# Power_Supply.net
KiCad netlist of a schematic drawn in Altium Designer
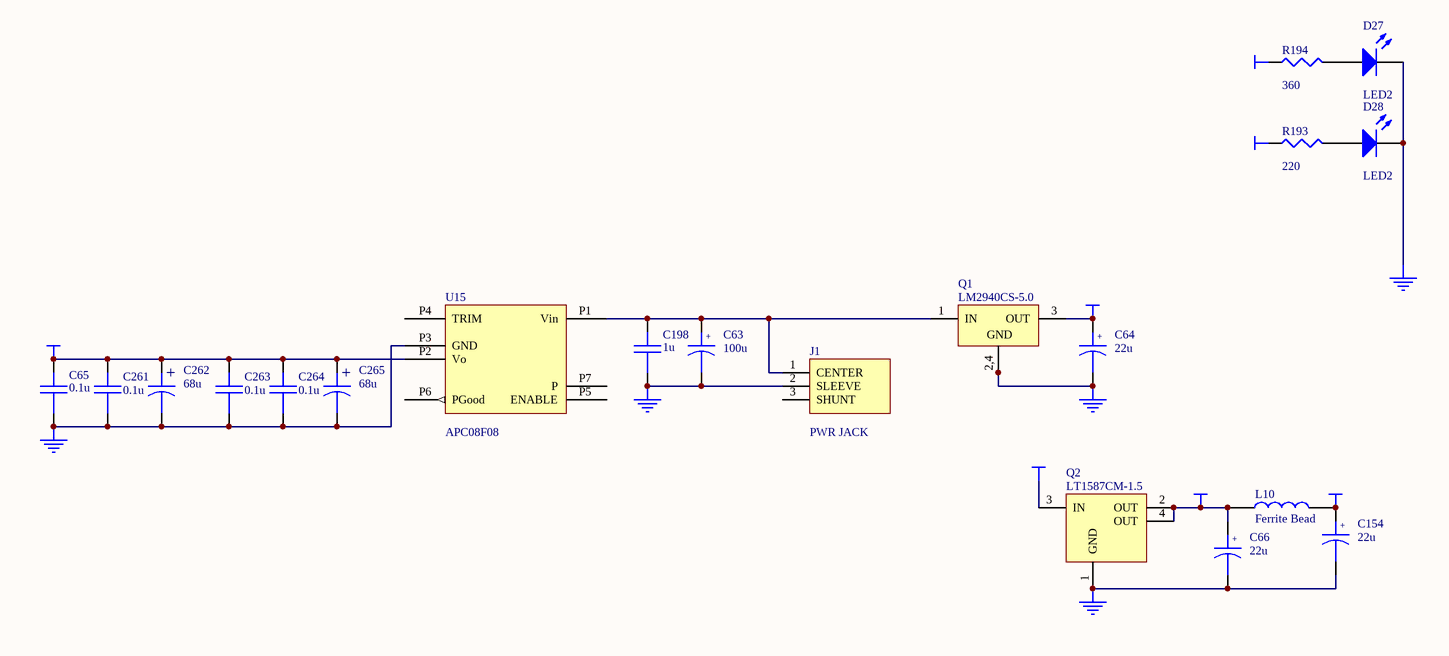
[diagram p0: Power Supply.SchDoc]

(export (version "E")
  (design (tool "Eeschema 10.0.6"))
  (components
    (comp (ref "C63")
      (value "100u")
      (footprint "7343")
      (libsource (lib "Cypress Molson") (part "CAPACITOR POL"))
    )
    (comp (ref "C64")
      (value "22u")
      (footprint "6032")
      (libsource (lib "Cypress Molson") (part "CAPACITOR POL"))
    )
    (comp (ref "C65")
      (value "~")
      (footprint "0603")
      (description "SMT CAP")
      (libsource (lib "Cypress Molson") (part "CAP"))
    )
    (comp (ref "C66")
      (value "22u")
      (footprint "6032")
      (libsource (lib "Cypress Molson") (part "CAPACITOR POL"))
    )
    (comp (ref "C154")
      (value "22u")
      (footprint "6032")
      (libsource (lib "Cypress Molson") (part "CAPACITOR POL"))
    )
    (comp (ref "C198")
      (value "~")
      (footprint "0805")
      (description "SMT CAP")
      (libsource (lib "Cypress Molson") (part "CAP"))
    )
    (comp (ref "C261")
      (value "~")
      (footprint "0603")
      (description "SMT CAP")
      (libsource (lib "Cypress Molson") (part "CAP"))
    )
    (comp (ref "C262") (value "68u") (footprint "6032") (libsource (lib "") (part "CAPACITOR POL_1")))
    (comp (ref "C263")
      (value "~")
      (footprint "0603")
      (description "SMT CAP")
      (libsource (lib "Cypress Molson") (part "CAP"))
    )
    (comp (ref "C264")
      (value "~")
      (footprint "0603")
      (description "SMT CAP")
      (libsource (lib "Cypress Molson") (part "CAP"))
    )
    (comp (ref "C265") (value "68u") (footprint "6032") (libsource (lib "") (part "CAPACITOR POL_1")))
    (comp (ref "D27")
      (value "LED2")
      (footprint "0603D")
      (description "Typical RED, GREEN, YELLOW, AMBER GaAs LED")
      (fields (field (name "MANUFACTURER") "Generic Components") (field (name "PUBLISHER") "Altium Limited"))
      (libsource (lib "Miscellaneous Devices") (part "LED2"))
    )
    (comp (ref "D28")
      (value "LED2")
      (footprint "0603D")
      (description "Typical RED, GREEN, YELLOW, AMBER GaAs LED")
      (fields (field (name "MANUFACTURER") "Generic Components") (field (name "PUBLISHER") "Altium Limited"))
      (libsource (lib "Miscellaneous Devices") (part "LED2"))
    )
    (comp (ref "J1")
      (value "PWR JACK")
      (footprint "RAPC712")
      (description "Power Jack")
      (libsource (lib "Schematic") (part "PWR JACK"))
    )
    (comp (ref "L10")
      (value "Ferrite Bead")
      (footprint "0603")
      (libsource (lib "Cypress Molson") (part "INDUCTOR1"))
    )
    (comp (ref "Q1")
      (value "LM2940CS-5.0")
      (footprint "SIP-G3/Y2.1")
      (description "1A Low-Dropout Regulator")
      (fields
        (field (name "MANUFACTURER") "National Semiconductor")
        (field (name "PUBLISHER") "Altium Limited")
      )
      (libsource (lib "Cypress Molson") (part "LM2940CS-5.0"))
    )
    (comp (ref "Q2")
      (value "LT1587CM-1.5")
      (footprint "DDPACK3")
      (description "3-Terminal Positive Regulator")
      (fields
        (field (name "MANUFACTURER") "National Semiconductor")
        (field (name "PUBLISHER") "Altium Limited")
      )
      (libsource (lib "Cypress Molson") (part "LT1587CM-1.5"))
    )
    (comp (ref "R193") (value "220") (footprint "0603") (libsource (lib "Cypress Molson") (part "RES1")))
    (comp (ref "R194") (value "360") (footprint "0603") (libsource (lib "Cypress Molson") (part "RES1")))
    (comp (ref "U15")
      (value "APC08F08")
      (footprint "APC08F08")
      (libsource (lib "Cypress Molson") (part "APC08F08"))
    )
  )
  (nets
    (net (code "1") (name "+1.5V") (class "Default")
      (node (ref "C66") (pin "1") (pinfunction "1_1") (pintype "passive"))
      (node (ref "L10") (pin "1") (pinfunction "1_1") (pintype "passive"))
      (node (ref "Q2") (pin "2") (pinfunction "OUT_2") (pintype "power_in"))
      (node (ref "Q2") (pin "4") (pinfunction "OUT_4") (pintype "power_in"))
    )
    (net (code "2") (name "+1.5VA") (class "Default")
      (node (ref "C154") (pin "1") (pinfunction "1_1") (pintype "passive"))
      (node (ref "L10") (pin "2") (pinfunction "2_2") (pintype "passive"))
    )
    (net (code "3") (name "+3.3V") (class "Default")
      (node (ref "C261") (pin "1") (pinfunction "1_1") (pintype "passive"))
      (node (ref "C262") (pin "1") (pinfunction "1_1") (pintype "passive"))
      (node (ref "C263") (pin "1") (pinfunction "1_1") (pintype "passive"))
      (node (ref "C264") (pin "1") (pinfunction "1_1") (pintype "passive"))
      (node (ref "C265") (pin "1") (pinfunction "1_1") (pintype "passive"))
      (node (ref "C65") (pin "1") (pinfunction "1_1") (pintype "passive"))
      (node (ref "Q2") (pin "3") (pinfunction "IN_3") (pintype "power_in"))
      (node (ref "R193") (pin "1") (pintype "passive"))
      (node (ref "U15") (pin "P2") (pinfunction "Vo_P2") (pintype "power_in"))
    )
    (net (code "4") (name "+5V") (class "Default")
      (node (ref "C64") (pin "1") (pinfunction "1_1") (pintype "passive"))
      (node (ref "Q1") (pin "3") (pinfunction "OUT_3") (pintype "power_in"))
      (node (ref "R194") (pin "1") (pintype "passive"))
    )
    (net (code "5") (name "GND") (class "Default")
      (node (ref "C154") (pin "2") (pinfunction "2_2") (pintype "passive"))
      (node (ref "C198") (pin "2") (pinfunction "2_2") (pintype "passive"))
      (node (ref "C261") (pin "2") (pinfunction "2_2") (pintype "passive"))
      (node (ref "C262") (pin "2") (pinfunction "2_2") (pintype "passive"))
      (node (ref "C263") (pin "2") (pinfunction "2_2") (pintype "passive"))
      (node (ref "C264") (pin "2") (pinfunction "2_2") (pintype "passive"))
      (node (ref "C265") (pin "2") (pinfunction "2_2") (pintype "passive"))
      (node (ref "C63") (pin "2") (pinfunction "2_2") (pintype "passive"))
      (node (ref "C64") (pin "2") (pinfunction "2_2") (pintype "passive"))
      (node (ref "C65") (pin "2") (pinfunction "2_2") (pintype "passive"))
      (node (ref "C66") (pin "2") (pinfunction "2_2") (pintype "passive"))
      (node (ref "D27") (pin "2") (pinfunction "K_2") (pintype "passive"))
      (node (ref "D28") (pin "2") (pinfunction "K_2") (pintype "passive"))
      (node (ref "J1") (pin "2") (pinfunction "SLEEVE_2") (pintype "passive"))
      (node (ref "Q1") (pin "2") (pinfunction "GND_2") (pintype "power_in"))
      (node (ref "Q1") (pin "4") (pinfunction "GND_4") (pintype "power_in"))
      (node (ref "Q2") (pin "1") (pinfunction "GND_1") (pintype "power_in"))
      (node (ref "U15") (pin "P3") (pinfunction "GND_P3") (pintype "power_in"))
    )
    (net (code "6") (name "Net-(D27-A)") (class "Default")
      (node (ref "D27") (pin "1") (pinfunction "A_1") (pintype "passive"))
      (node (ref "R194") (pin "2") (pintype "passive"))
    )
    (net (code "7") (name "Net-(D28-A)") (class "Default")
      (node (ref "D28") (pin "1") (pinfunction "A_1") (pintype "passive"))
      (node (ref "R193") (pin "2") (pintype "passive"))
    )
    (net (code "8") (name "Net-(J1-CENTER)") (class "Default")
      (node (ref "C198") (pin "1") (pinfunction "1_1") (pintype "passive"))
      (node (ref "C63") (pin "1") (pinfunction "1_1") (pintype "passive"))
      (node (ref "J1") (pin "1") (pinfunction "CENTER_1") (pintype "passive"))
      (node (ref "Q1") (pin "1") (pinfunction "IN_1") (pintype "power_in"))
      (node (ref "U15") (pin "P1") (pinfunction "Vin_P1") (pintype "power_in"))
    )
    (net (code "9") (name "unconnected-(J1-SHUNT-Pad3)") (class "Default")
      (node (ref "J1") (pin "3") (pinfunction "SHUNT_3") (pintype "passive"))
    )
    (net (code "10") (name "unconnected-(U15-ENABLE-PadP5)") (class "Default")
      (node (ref "U15") (pin "P5") (pinfunction "ENABLE_P5") (pintype "passive"))
    )
    (net (code "11") (name "unconnected-(U15-P-PadP7)") (class "Default")
      (node (ref "U15") (pin "P7") (pinfunction "P_P7") (pintype "passive"))
    )
    (net (code "12") (name "unconnected-(U15-PGood-PadP6)") (class "Default")
      (node (ref "U15") (pin "P6") (pinfunction "PGood_P6") (pintype "output"))
    )
    (net (code "13") (name "unconnected-(U15-TRIM-PadP4)") (class "Default")
      (node (ref "U15") (pin "P4") (pinfunction "TRIM_P4") (pintype "passive"))
    )
  )
)
